# mbed_programmer.net
KiCad netlist of a schematic drawn in EAGLE
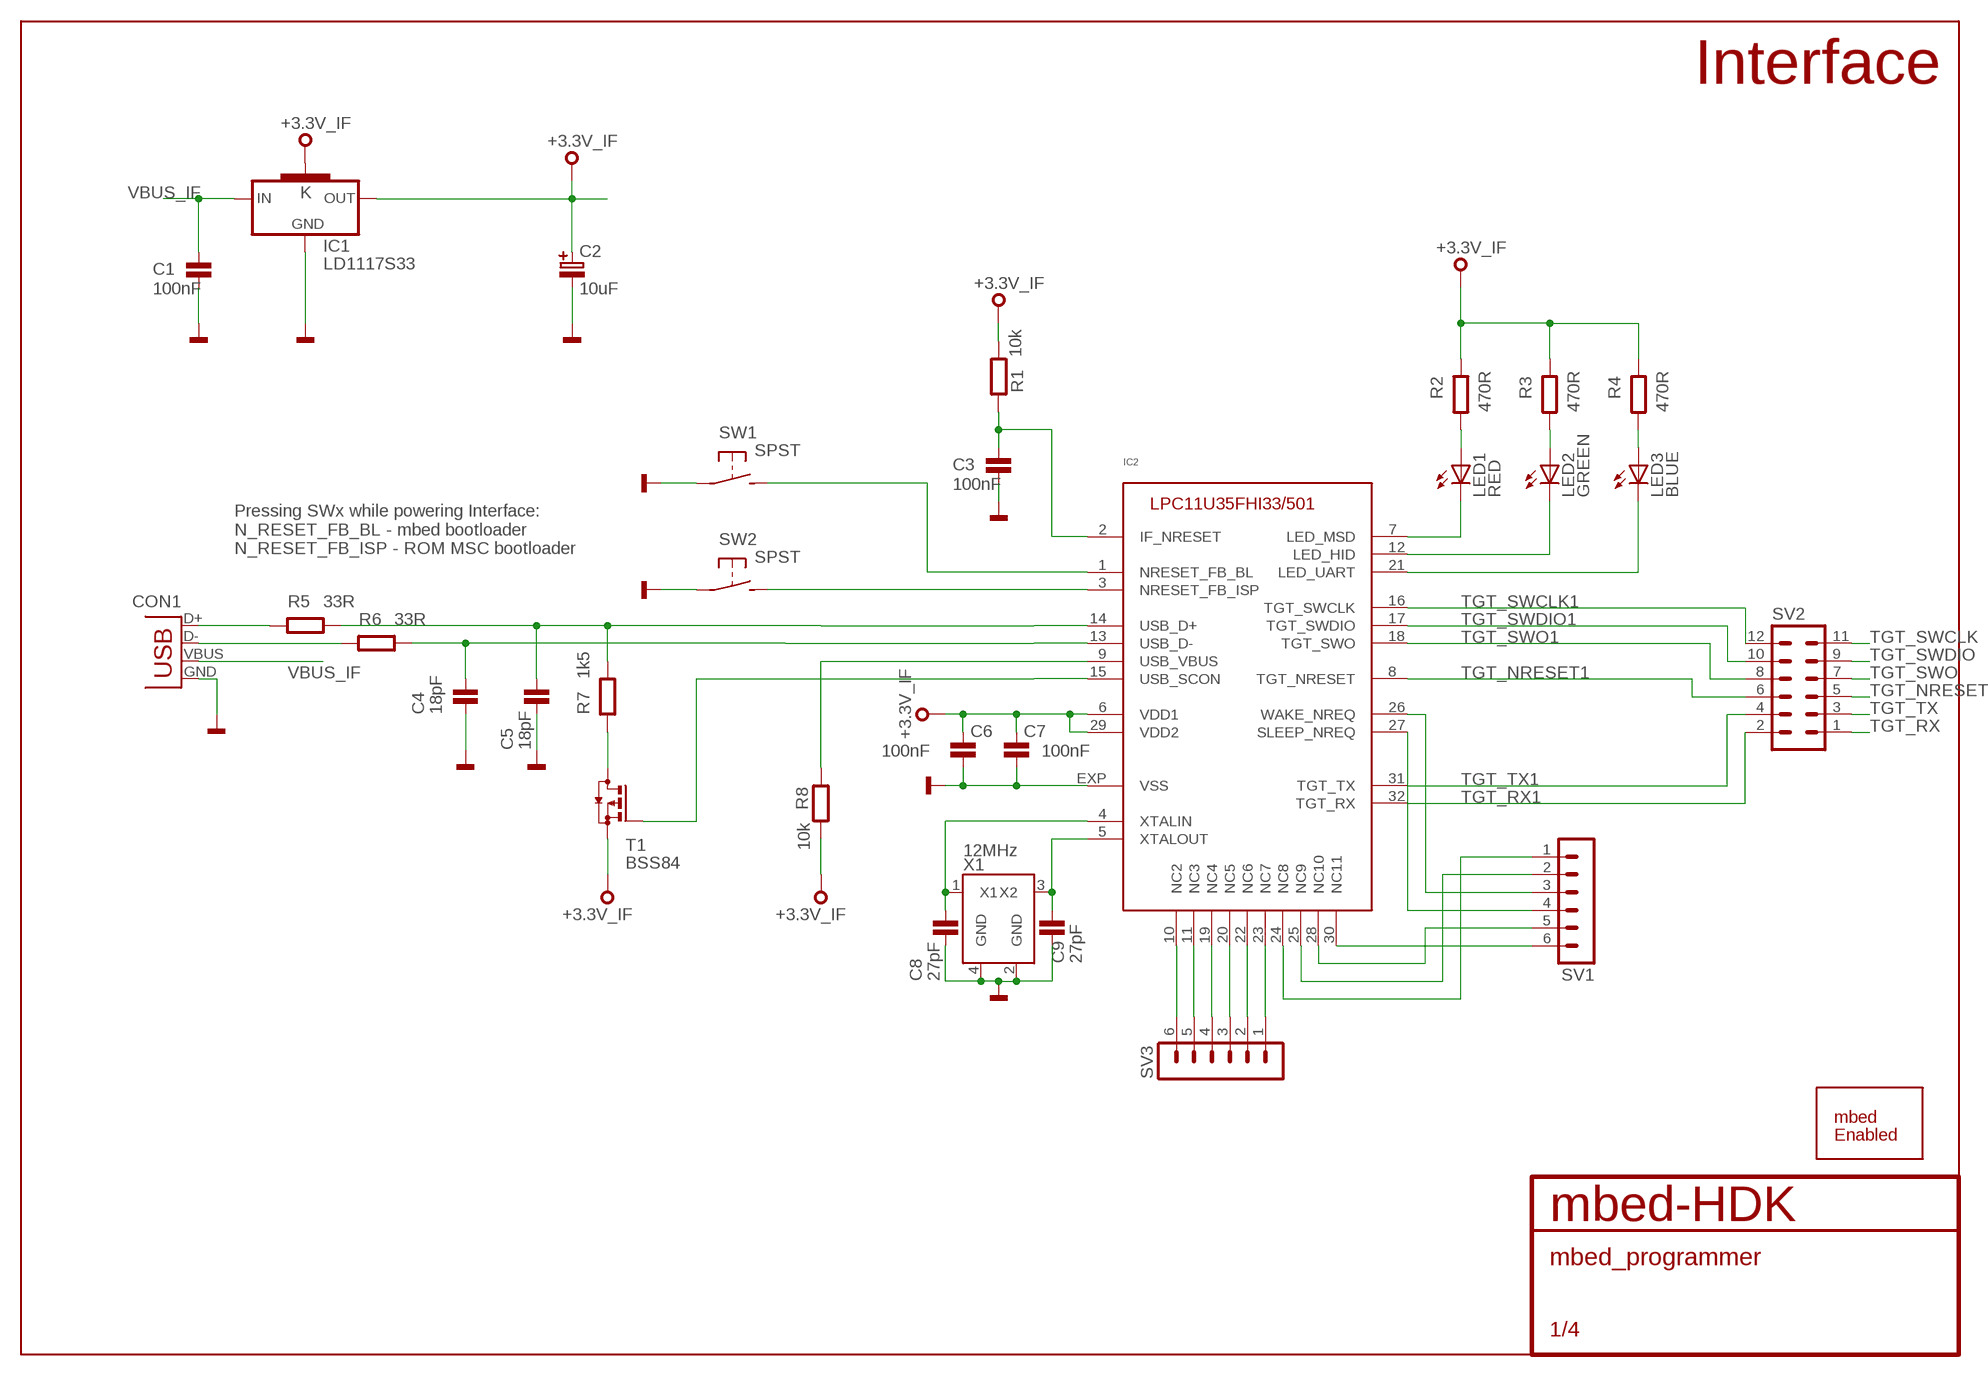
[diagram p0: schematic, sheet 1]
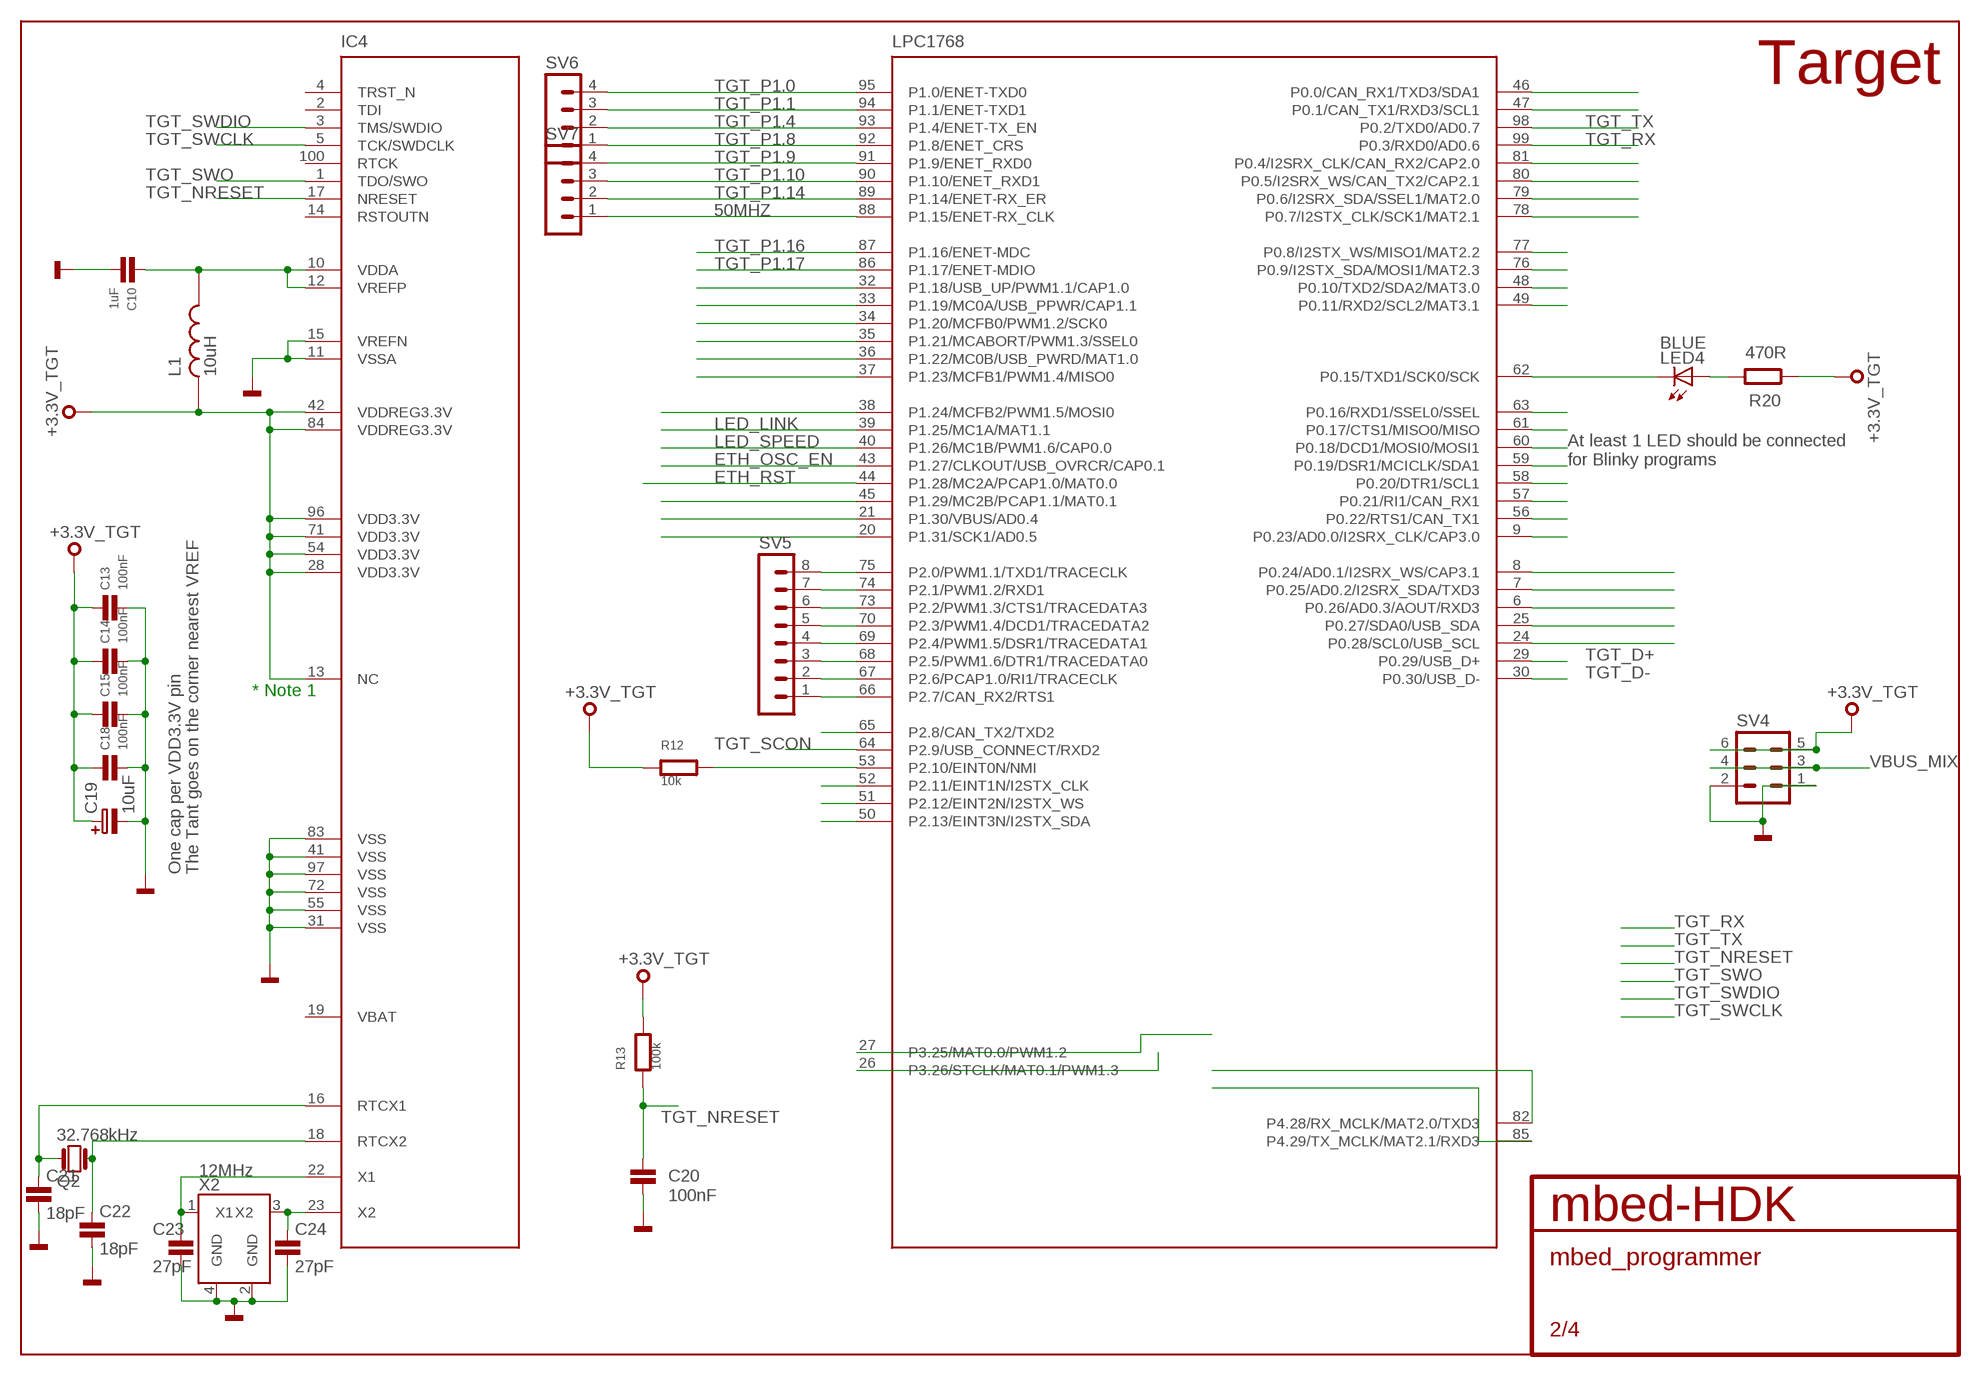
[diagram p1: schematic, sheet 2]
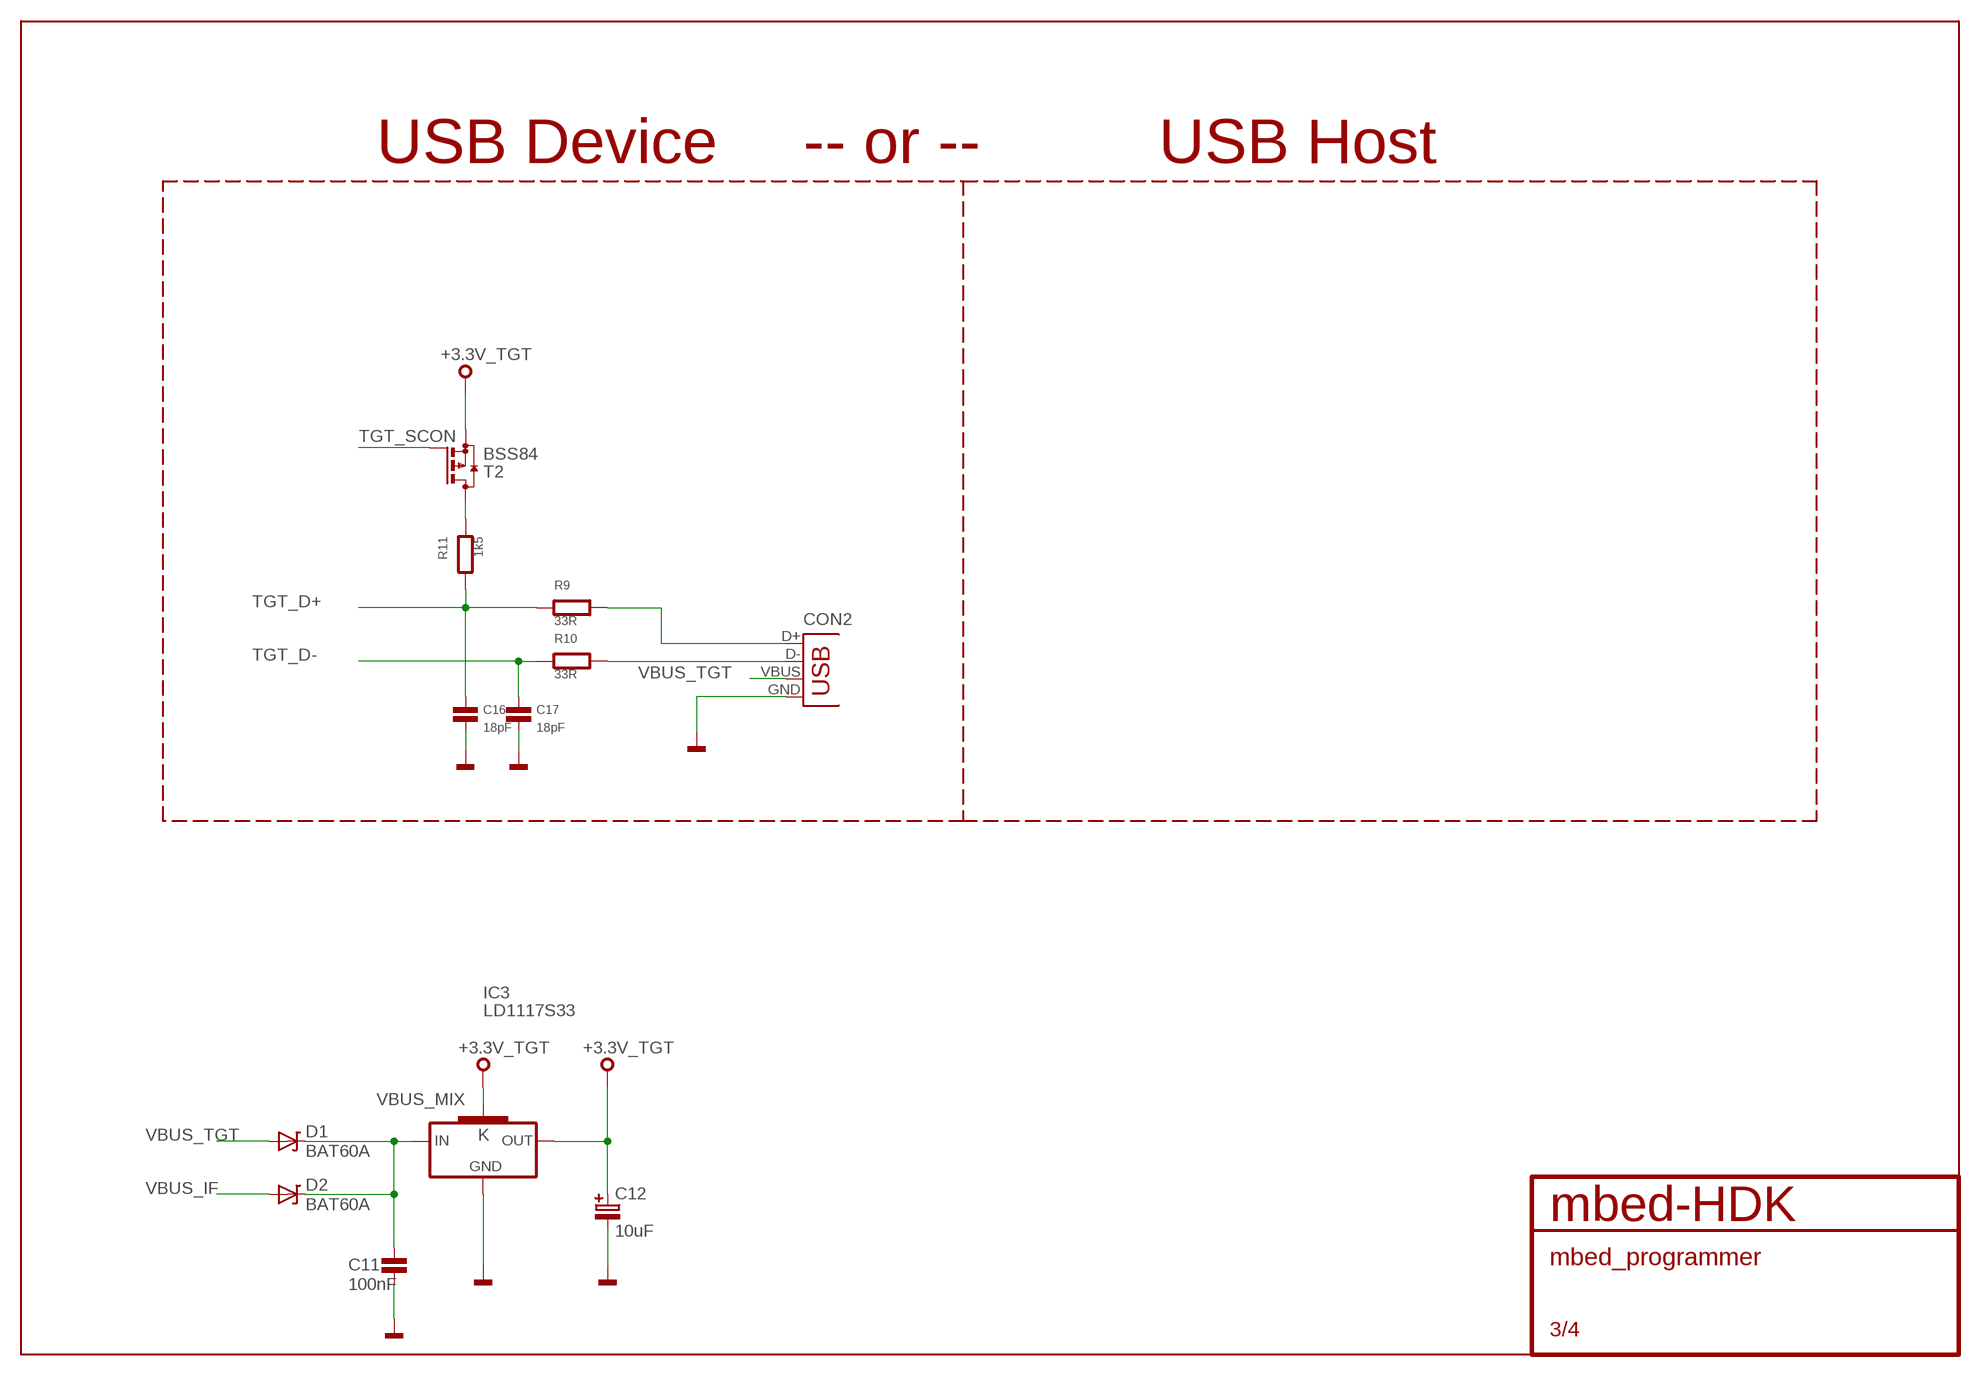
[diagram p2: schematic, sheet 3]
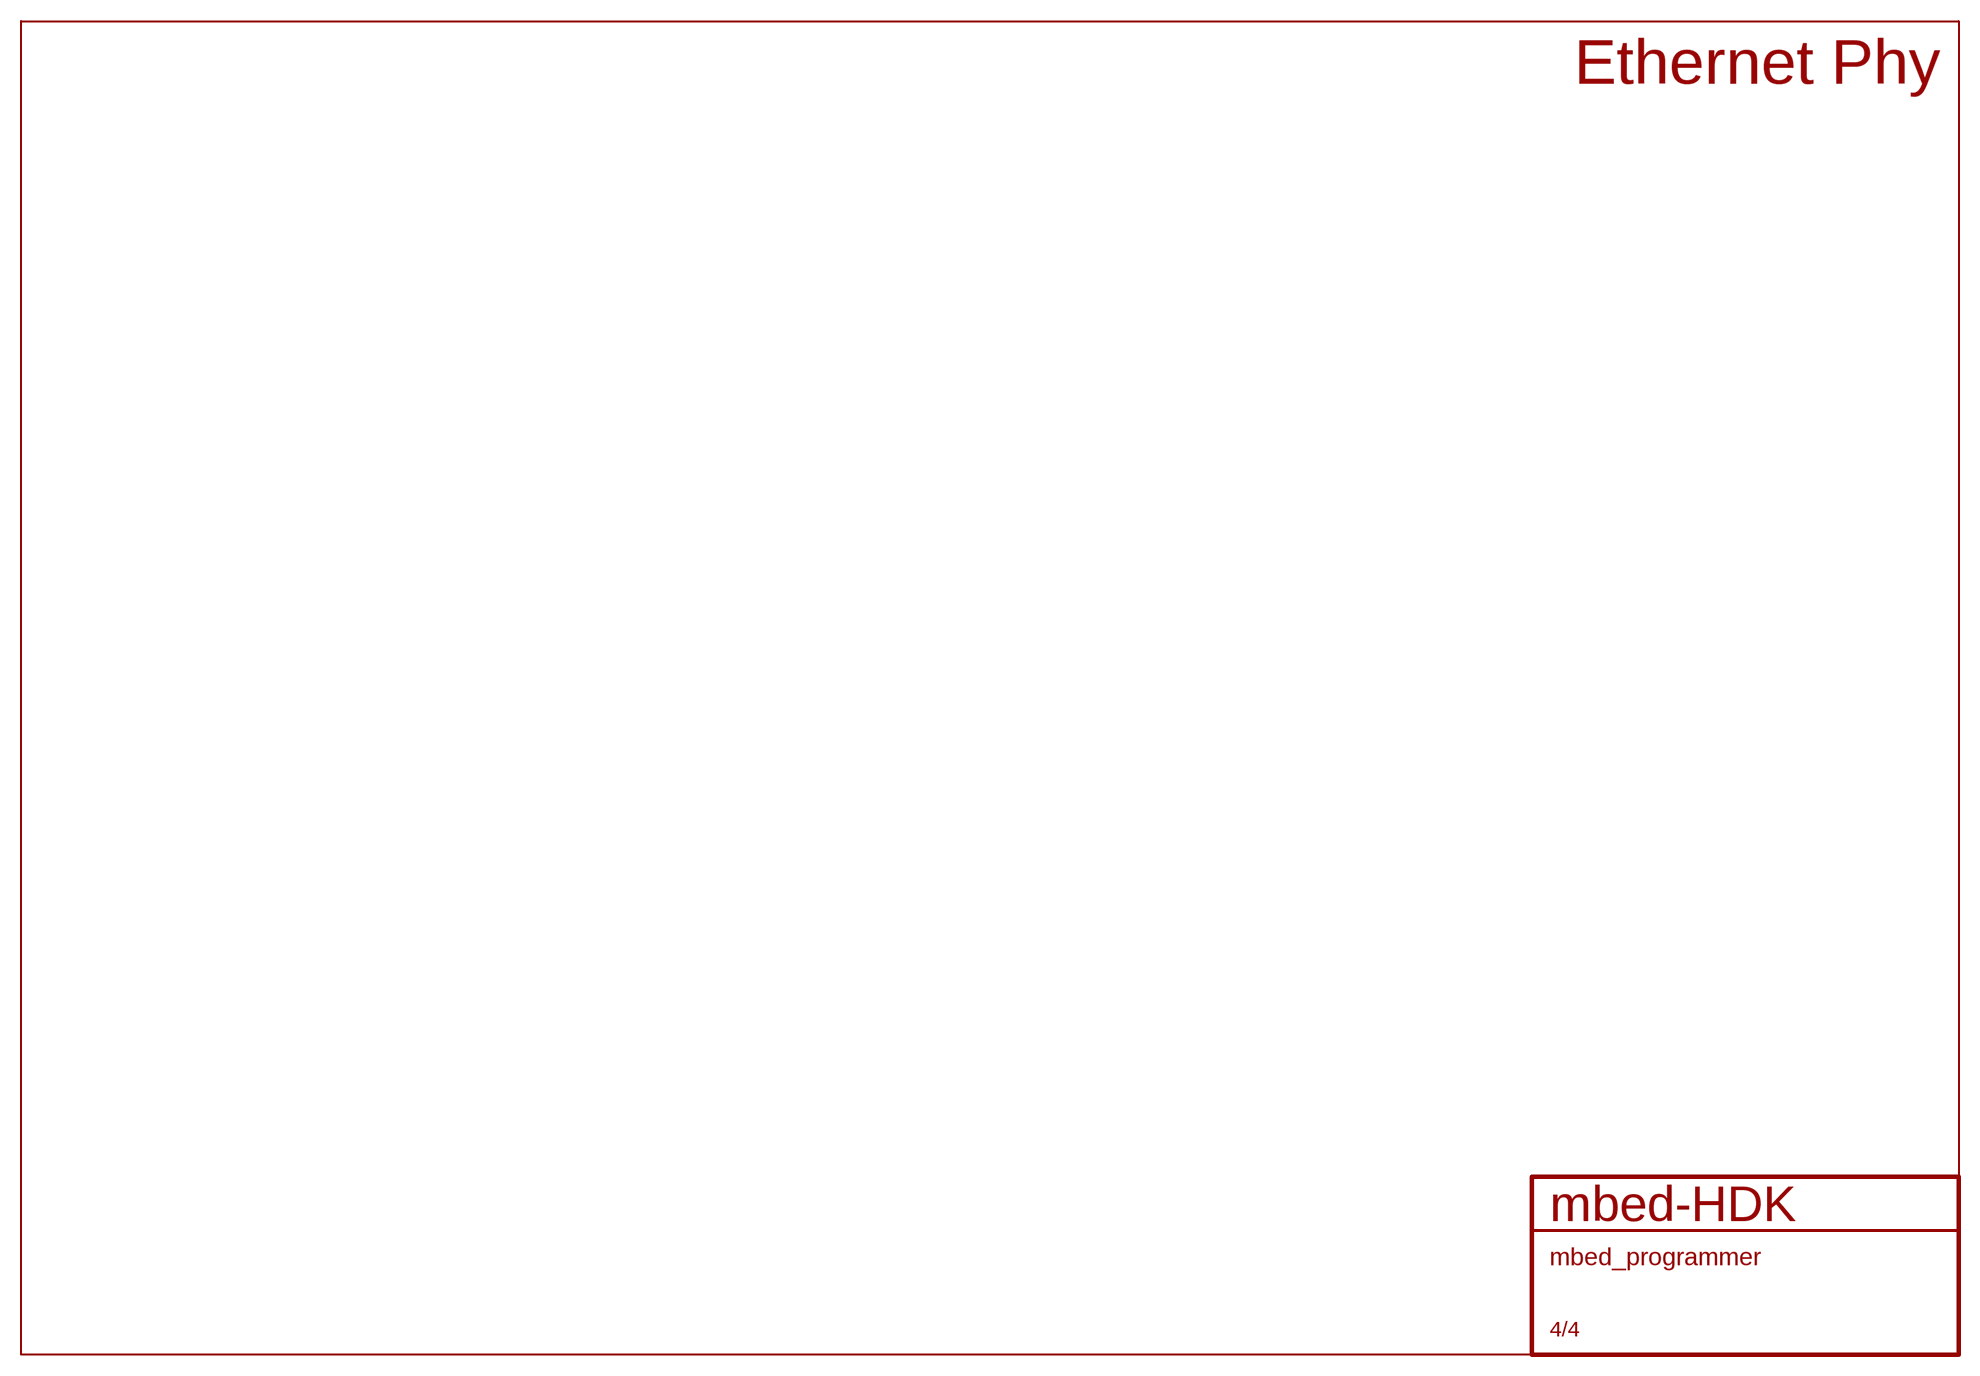
[diagram p3: schematic, sheet 4]

(export (version "E")
  (design (tool "Eeschema 10.0.6"))
  (components
    (comp (ref "C10")
      (value "1uF")
      (footprint "eagle-import:0603")
      (libsource (lib "eagle-import") (part "C0603"))
    )
    (comp (ref "C13")
      (value "100nF")
      (footprint "eagle-import:0603")
      (libsource (lib "eagle-import") (part "C0603"))
    )
    (comp (ref "C14")
      (value "100nF")
      (footprint "eagle-import:0603")
      (libsource (lib "eagle-import") (part "C0603"))
    )
    (comp (ref "C15")
      (value "100nF")
      (footprint "eagle-import:0603")
      (libsource (lib "eagle-import") (part "C0603"))
    )
    (comp (ref "C18")
      (value "100nF")
      (footprint "eagle-import:0603")
      (libsource (lib "eagle-import") (part "C0603"))
    )
    (comp (ref "C19")
      (value "10uF")
      (footprint "eagle-import:CASE-B")
      (libsource (lib "eagle-import") (part "C-POLB"))
    )
    (comp (ref "C20")
      (value "100nF")
      (footprint "eagle-import:0603")
      (libsource (lib "eagle-import") (part "C0603"))
    )
    (comp (ref "C21")
      (value "18pF")
      (footprint "eagle-import:0603")
      (libsource (lib "eagle-import") (part "C0603"))
    )
    (comp (ref "C22")
      (value "18pF")
      (footprint "eagle-import:0603")
      (libsource (lib "eagle-import") (part "C0603"))
    )
    (comp (ref "C23")
      (value "27pF")
      (footprint "eagle-import:0603")
      (libsource (lib "eagle-import") (part "C0603"))
    )
    (comp (ref "C24")
      (value "27pF")
      (footprint "eagle-import:0603")
      (libsource (lib "eagle-import") (part "C0603"))
    )
    (comp (ref "IC4")
      (value "LPC1768")
      (footprint "eagle-import:LQFP100")
      (libsource (lib "eagle-import") (part "LPC1768"))
    )
    (comp (ref "L1")
      (value "10uH")
      (footprint "eagle-import:0603")
      (libsource (lib "eagle-import") (part "L"))
    )
    (comp (ref "LED4")
      (value "BLUE")
      (footprint "eagle-import:CHIPLED_0603")
      (libsource (lib "eagle-import") (part "LED0603"))
    )
    (comp (ref "Q2")
      (value "32.768kHz")
      (footprint "eagle-import:FC135")
      (libsource (lib "eagle-import") (part "Q_FC135"))
    )
    (comp (ref "R12")
      (value "10k")
      (footprint "eagle-import:0603")
      (libsource (lib "eagle-import") (part "R0603"))
    )
    (comp (ref "R13")
      (value "100k")
      (footprint "eagle-import:0603")
      (libsource (lib "eagle-import") (part "R0603"))
    )
    (comp (ref "R20")
      (value "470R")
      (footprint "eagle-import:0603")
      (libsource (lib "eagle-import") (part "R0603"))
    )
    (comp (ref "SV4")
      (value "MA03-2")
      (footprint "eagle-import:MA03-2")
      (libsource (lib "eagle-import") (part "MA03-2"))
    )
    (comp (ref "SV5")
      (value "MA08-1")
      (footprint "eagle-import:MA08-1")
      (libsource (lib "eagle-import") (part "MA08-1"))
    )
    (comp (ref "SV6")
      (value "MA04-1")
      (footprint "eagle-import:MA04-1")
      (libsource (lib "eagle-import") (part "MA04-1"))
    )
    (comp (ref "SV7")
      (value "MA04-1")
      (footprint "eagle-import:MA04-1")
      (libsource (lib "eagle-import") (part "MA04-1"))
    )
    (comp (ref "X2")
      (value "12MHz")
      (footprint "eagle-import:OSC_CMD_32_25")
      (libsource (lib "eagle-import") (part "ABM8"))
    )
    (comp (ref "C1")
      (value "100nF")
      (footprint "eagle-import:0603")
      (libsource (lib "eagle-import") (part "C0603"))
    )
    (comp (ref "C2")
      (value "10uF")
      (footprint "eagle-import:CASE-B")
      (libsource (lib "eagle-import") (part "C-POLB"))
    )
    (comp (ref "C3")
      (value "100nF")
      (footprint "eagle-import:0603")
      (libsource (lib "eagle-import") (part "C0603"))
    )
    (comp (ref "C4")
      (value "18pF")
      (footprint "eagle-import:0603")
      (libsource (lib "eagle-import") (part "C0603"))
    )
    (comp (ref "C5")
      (value "18pF")
      (footprint "eagle-import:0603")
      (libsource (lib "eagle-import") (part "C0603"))
    )
    (comp (ref "C6")
      (value "100nF")
      (footprint "eagle-import:0603")
      (libsource (lib "eagle-import") (part "C0603"))
    )
    (comp (ref "C7")
      (value "100nF")
      (footprint "eagle-import:0603")
      (libsource (lib "eagle-import") (part "C0603"))
    )
    (comp (ref "C8")
      (value "27pF")
      (footprint "eagle-import:0603")
      (libsource (lib "eagle-import") (part "C0603"))
    )
    (comp (ref "C9")
      (value "27pF")
      (footprint "eagle-import:0603")
      (libsource (lib "eagle-import") (part "C0603"))
    )
    (comp (ref "CON1")
      (value "USB-MB-S")
      (footprint "eagle-import:USB-MB-S")
      (libsource (lib "eagle-import") (part "USB-MB-S"))
    )
    (comp (ref "IC1")
      (value "LD1117S33")
      (footprint "eagle-import:SOT223")
      (libsource (lib "eagle-import") (part "LD1117S33"))
    )
    (comp (ref "IC2")
      (value "IF-LPC11U35")
      (footprint "eagle-import:HVQFN33")
      (libsource (lib "eagle-import") (part "IF-LPC11U35"))
    )
    (comp (ref "LED1")
      (value "RED")
      (footprint "eagle-import:CHIPLED_0603")
      (libsource (lib "eagle-import") (part "LED0603"))
    )
    (comp (ref "LED2")
      (value "GREEN")
      (footprint "eagle-import:CHIPLED_0603")
      (libsource (lib "eagle-import") (part "LED0603"))
    )
    (comp (ref "LED3")
      (value "BLUE")
      (footprint "eagle-import:CHIPLED_0603")
      (libsource (lib "eagle-import") (part "LED0603"))
    )
    (comp (ref "R1")
      (value "10k")
      (footprint "eagle-import:0603")
      (libsource (lib "eagle-import") (part "R0603"))
    )
    (comp (ref "R2")
      (value "470R")
      (footprint "eagle-import:0603")
      (libsource (lib "eagle-import") (part "R0603"))
    )
    (comp (ref "R3")
      (value "470R")
      (footprint "eagle-import:0603")
      (libsource (lib "eagle-import") (part "R0603"))
    )
    (comp (ref "R4")
      (value "470R")
      (footprint "eagle-import:0603")
      (libsource (lib "eagle-import") (part "R0603"))
    )
    (comp (ref "R5")
      (value "33R")
      (footprint "eagle-import:0603")
      (libsource (lib "eagle-import") (part "R0603"))
    )
    (comp (ref "R6")
      (value "33R")
      (footprint "eagle-import:0603")
      (libsource (lib "eagle-import") (part "R0603"))
    )
    (comp (ref "R7")
      (value "1k5")
      (footprint "eagle-import:0603")
      (libsource (lib "eagle-import") (part "R0603"))
    )
    (comp (ref "R8")
      (value "10k")
      (footprint "eagle-import:0603")
      (libsource (lib "eagle-import") (part "R0603"))
    )
    (comp (ref "SS1")
      (value "MBED-ENABLED-LOGOMEDIUM")
      (footprint "eagle-import:MBED-ENABLED-LOGO-500X500-MIL")
      (libsource (lib "eagle-import") (part "MBED-ENABLED-LOGOMEDIUM"))
    )
    (comp (ref "SV1")
      (value "MA06-1")
      (footprint "eagle-import:MA06-1")
      (libsource (lib "eagle-import") (part "MA06-1"))
    )
    (comp (ref "SV2")
      (value "MA06-2")
      (footprint "eagle-import:MA06-2")
      (libsource (lib "eagle-import") (part "MA06-2"))
    )
    (comp (ref "SV3")
      (value "MA06-1")
      (footprint "eagle-import:MA06-1")
      (libsource (lib "eagle-import") (part "MA06-1"))
    )
    (comp (ref "SW1")
      (value "SPST")
      (footprint "eagle-import:DTSM-32S-B")
      (libsource (lib "eagle-import") (part "SPST"))
    )
    (comp (ref "SW2")
      (value "SPST")
      (footprint "eagle-import:DTSM-32S-B")
      (libsource (lib "eagle-import") (part "SPST"))
    )
    (comp (ref "T1")
      (value "BSS84")
      (footprint "eagle-import:SOT23")
      (libsource (lib "eagle-import") (part "BSS84"))
    )
    (comp (ref "X1")
      (value "12MHz")
      (footprint "eagle-import:OSC_CMD_32_25")
      (libsource (lib "eagle-import") (part "ABM8"))
    )
    (comp (ref "C11")
      (value "100nF")
      (footprint "eagle-import:0603")
      (libsource (lib "eagle-import") (part "C0603"))
    )
    (comp (ref "C12")
      (value "10uF")
      (footprint "eagle-import:CASE-B")
      (libsource (lib "eagle-import") (part "C-POLB"))
    )
    (comp (ref "C16")
      (value "18pF")
      (footprint "eagle-import:0603")
      (libsource (lib "eagle-import") (part "C0603"))
    )
    (comp (ref "C17")
      (value "18pF")
      (footprint "eagle-import:0603")
      (libsource (lib "eagle-import") (part "C0603"))
    )
    (comp (ref "CON2")
      (value "USB-MB-S")
      (footprint "eagle-import:USB-MB-S")
      (libsource (lib "eagle-import") (part "USB-MB-S"))
    )
    (comp (ref "D1")
      (value "BAT60A")
      (footprint "eagle-import:BAT60A")
      (libsource (lib "eagle-import") (part "BAT60A"))
    )
    (comp (ref "D2")
      (value "BAT60A")
      (footprint "eagle-import:BAT60A")
      (libsource (lib "eagle-import") (part "BAT60A"))
    )
    (comp (ref "IC3")
      (value "LD1117S33")
      (footprint "eagle-import:SOT223")
      (libsource (lib "eagle-import") (part "LD1117S33"))
    )
    (comp (ref "R9")
      (value "33R")
      (footprint "eagle-import:0603")
      (libsource (lib "eagle-import") (part "R0603"))
    )
    (comp (ref "R10")
      (value "33R")
      (footprint "eagle-import:0603")
      (libsource (lib "eagle-import") (part "R0603"))
    )
    (comp (ref "R11")
      (value "1k5")
      (footprint "eagle-import:0603")
      (libsource (lib "eagle-import") (part "R0603"))
    )
    (comp (ref "T2")
      (value "BSS84")
      (footprint "eagle-import:SOT23")
      (libsource (lib "eagle-import") (part "BSS84"))
    )
  )
  (nets
    (net (code "1") (name "+3.3V_IF") (class "Default")
      (node (ref "C2") (pin "1") (pinfunction "1_1") (pintype "passive"))
      (node (ref "C6") (pin "1") (pinfunction "P$1_1") (pintype "passive"))
      (node (ref "C7") (pin "1") (pinfunction "P$1_1") (pintype "passive"))
      (node (ref "IC1") (pin "2") (pinfunction "OUT_2") (pintype "passive"))
      (node (ref "IC1") (pin "4") (pinfunction "K_4") (pintype "passive"))
      (node (ref "IC2") (pin "29") (pinfunction "VDD2_29") (pintype "bidirectional"))
      (node (ref "IC2") (pin "6") (pinfunction "VDD1_6") (pintype "bidirectional"))
      (node (ref "R1") (pin "2") (pinfunction "P$2_2") (pintype "passive"))
      (node (ref "R2") (pin "1") (pinfunction "P$1_1") (pintype "passive"))
      (node (ref "R3") (pin "1") (pinfunction "P$1_1") (pintype "passive"))
      (node (ref "R4") (pin "1") (pinfunction "P$1_1") (pintype "passive"))
      (node (ref "R8") (pin "2") (pinfunction "P$2_2") (pintype "passive"))
      (node (ref "T1") (pin "2") (pinfunction "S_2") (pintype "passive"))
    )
    (net (code "2") (name "+3.3V_TGT") (class "Default")
      (node (ref "C12") (pin "1") (pinfunction "1_1") (pintype "passive"))
      (node (ref "C13") (pin "1") (pinfunction "P$1_1") (pintype "passive"))
      (node (ref "C14") (pin "1") (pinfunction "P$1_1") (pintype "passive"))
      (node (ref "C15") (pin "1") (pinfunction "P$1_1") (pintype "passive"))
      (node (ref "C18") (pin "1") (pinfunction "P$1_1") (pintype "passive"))
      (node (ref "C19") (pin "1") (pinfunction "1_1") (pintype "passive"))
      (node (ref "IC3") (pin "2") (pinfunction "OUT_2") (pintype "passive"))
      (node (ref "IC3") (pin "4") (pinfunction "K_4") (pintype "passive"))
      (node (ref "IC4") (pin "13") (pinfunction "NC_13") (pintype "bidirectional"))
      (node (ref "IC4") (pin "28") (pinfunction "VDD3.3V_28") (pintype "bidirectional"))
      (node (ref "IC4") (pin "42") (pinfunction "VDDREG3.3V_42") (pintype "bidirectional"))
      (node (ref "IC4") (pin "54") (pinfunction "VDD3.3V_54") (pintype "bidirectional"))
      (node (ref "IC4") (pin "71") (pinfunction "VDD3.3V_71") (pintype "bidirectional"))
      (node (ref "IC4") (pin "84") (pinfunction "VDDREG3.3V_84") (pintype "bidirectional"))
      (node (ref "IC4") (pin "96") (pinfunction "VDD3.3V_96") (pintype "bidirectional"))
      (node (ref "L1") (pin "1") (pinfunction "P$1_1") (pintype "bidirectional"))
      (node (ref "R12") (pin "1") (pinfunction "P$1_1") (pintype "passive"))
      (node (ref "R13") (pin "2") (pinfunction "P$2_2") (pintype "passive"))
      (node (ref "R20") (pin "1") (pinfunction "P$1_1") (pintype "passive"))
      (node (ref "SV4") (pin "5") (pinfunction "5_5") (pintype "passive"))
      (node (ref "SV4") (pin "6") (pinfunction "6_6") (pintype "passive"))
      (node (ref "T2") (pin "2") (pinfunction "S_2") (pintype "passive"))
    )
    (net (code "3") (name "50MHZ") (class "Default")
      (node (ref "IC4") (pin "88") (pinfunction "P1.15/ENET-RX_CLK_88") (pintype "bidirectional"))
      (node (ref "SV7") (pin "1") (pinfunction "1_1") (pintype "passive"))
    )
    (net (code "4") (name "ETH_OSC_EN") (class "Default")
      (node (ref "IC4") (pin "43") (pinfunction "P1.27/CLKOUT/USB_OVRCR/CAP0.1_43") (pintype "bidirectional"))
    )
    (net (code "5") (name "ETH_RST") (class "Default")
      (node (ref "IC4") (pin "44") (pinfunction "P1.28/MC2A/PCAP1.0/MAT0.0_44") (pintype "bidirectional"))
    )
    (net (code "6") (name "GND") (class "Default")
      (node (ref "C1") (pin "2") (pinfunction "P$2_2") (pintype "passive"))
      (node (ref "C10") (pin "2") (pinfunction "P$2_2") (pintype "passive"))
      (node (ref "C11") (pin "2") (pinfunction "P$2_2") (pintype "passive"))
      (node (ref "C12") (pin "2") (pinfunction "2_2") (pintype "passive"))
      (node (ref "C13") (pin "2") (pinfunction "P$2_2") (pintype "passive"))
      (node (ref "C14") (pin "2") (pinfunction "P$2_2") (pintype "passive"))
      (node (ref "C15") (pin "2") (pinfunction "P$2_2") (pintype "passive"))
      (node (ref "C16") (pin "2") (pinfunction "P$2_2") (pintype "passive"))
      (node (ref "C17") (pin "2") (pinfunction "P$2_2") (pintype "passive"))
      (node (ref "C18") (pin "2") (pinfunction "P$2_2") (pintype "passive"))
      (node (ref "C19") (pin "2") (pinfunction "2_2") (pintype "passive"))
      (node (ref "C2") (pin "2") (pinfunction "2_2") (pintype "passive"))
      (node (ref "C20") (pin "1") (pinfunction "P$1_1") (pintype "passive"))
      (node (ref "C21") (pin "1") (pinfunction "P$1_1") (pintype "passive"))
      (node (ref "C22") (pin "1") (pinfunction "P$1_1") (pintype "passive"))
      (node (ref "C23") (pin "1") (pinfunction "P$1_1") (pintype "passive"))
      (node (ref "C24") (pin "1") (pinfunction "P$1_1") (pintype "passive"))
      (node (ref "C3") (pin "2") (pinfunction "P$2_2") (pintype "passive"))
      (node (ref "C4") (pin "2") (pinfunction "P$2_2") (pintype "passive"))
      (node (ref "C5") (pin "2") (pinfunction "P$2_2") (pintype "passive"))
      (node (ref "C6") (pin "2") (pinfunction "P$2_2") (pintype "passive"))
      (node (ref "C7") (pin "2") (pinfunction "P$2_2") (pintype "passive"))
      (node (ref "C8") (pin "2") (pinfunction "P$2_2") (pintype "passive"))
      (node (ref "C9") (pin "2") (pinfunction "P$2_2") (pintype "passive"))
      (node (ref "CON1") (pin "GND") (pinfunction "GND_GND") (pintype "bidirectional"))
      (node (ref "CON2") (pin "GND") (pinfunction "GND_GND") (pintype "bidirectional"))
      (node (ref "IC1") (pin "1") (pinfunction "GND_1") (pintype "input"))
      (node (ref "IC2") (pin "EXP") (pinfunction "VSS_EXP") (pintype "bidirectional"))
      (node (ref "IC3") (pin "1") (pinfunction "GND_1") (pintype "input"))
      (node (ref "IC4") (pin "11") (pinfunction "VSSA_11") (pintype "bidirectional"))
      (node (ref "IC4") (pin "15") (pinfunction "VREFN_15") (pintype "bidirectional"))
      (node (ref "IC4") (pin "31") (pinfunction "VSS_31") (pintype "bidirectional"))
      (node (ref "IC4") (pin "41") (pinfunction "VSS_41") (pintype "bidirectional"))
      (node (ref "IC4") (pin "55") (pinfunction "VSS_55") (pintype "bidirectional"))
      (node (ref "IC4") (pin "72") (pinfunction "VSS_72") (pintype "bidirectional"))
      (node (ref "IC4") (pin "83") (pinfunction "VSS_83") (pintype "bidirectional"))
      (node (ref "IC4") (pin "97") (pinfunction "VSS_97") (pintype "bidirectional"))
      (node (ref "SV4") (pin "1") (pinfunction "1_1") (pintype "passive"))
      (node (ref "SV4") (pin "2") (pinfunction "2_2") (pintype "passive"))
      (node (ref "SW1") (pin "P$1") (pinfunction "P_P$1") (pintype "passive"))
      (node (ref "SW2") (pin "P$1") (pinfunction "P_P$1") (pintype "passive"))
      (node (ref "X1") (pin "2") (pinfunction "GND_2") (pintype "bidirectional"))
      (node (ref "X1") (pin "4") (pinfunction "GND_4") (pintype "bidirectional"))
      (node (ref "X2") (pin "2") (pinfunction "GND_2") (pintype "bidirectional"))
      (node (ref "X2") (pin "4") (pinfunction "GND_4") (pintype "bidirectional"))
    )
    (net (code "7") (name "LED_LINK") (class "Default")
      (node (ref "IC4") (pin "39") (pinfunction "P1.25/MC1A/MAT1.1_39") (pintype "bidirectional"))
    )
    (net (code "8") (name "LED_SPEED") (class "Default")
      (node (ref "IC4") (pin "40") (pinfunction "P1.26/MC1B/PWM1.6/CAP0.0_40") (pintype "bidirectional"))
    )
    (net (code "9") (name "Net-(C3-P$1)") (class "Default")
      (node (ref "C3") (pin "1") (pinfunction "P$1_1") (pintype "passive"))
      (node (ref "IC2") (pin "2") (pinfunction "IF_NRESET_2") (pintype "bidirectional"))
      (node (ref "R1") (pin "1") (pinfunction "P$1_1") (pintype "passive"))
    )
    (net (code "10") (name "Net-(C4-P$1)") (class "Default")
      (node (ref "C4") (pin "1") (pinfunction "P$1_1") (pintype "passive"))
      (node (ref "IC2") (pin "13") (pinfunction "USB_D-_13") (pintype "bidirectional"))
      (node (ref "R6") (pin "2") (pinfunction "P$2_2") (pintype "passive"))
    )
    (net (code "11") (name "Net-(C5-P$1)") (class "Default")
      (node (ref "C5") (pin "1") (pinfunction "P$1_1") (pintype "passive"))
      (node (ref "IC2") (pin "14") (pinfunction "USB_D+_14") (pintype "bidirectional"))
      (node (ref "R5") (pin "2") (pinfunction "P$2_2") (pintype "passive"))
      (node (ref "R7") (pin "2") (pinfunction "P$2_2") (pintype "passive"))
    )
    (net (code "12") (name "Net-(C8-P$1)") (class "Default")
      (node (ref "C8") (pin "1") (pinfunction "P$1_1") (pintype "passive"))
      (node (ref "IC2") (pin "4") (pinfunction "XTALIN_4") (pintype "bidirectional"))
      (node (ref "X1") (pin "1") (pinfunction "X1_1") (pintype "bidirectional"))
    )
    (net (code "13") (name "Net-(C9-P$1)") (class "Default")
      (node (ref "C9") (pin "1") (pinfunction "P$1_1") (pintype "passive"))
      (node (ref "IC2") (pin "5") (pinfunction "XTALOUT_5") (pintype "bidirectional"))
      (node (ref "X1") (pin "3") (pinfunction "X2_3") (pintype "bidirectional"))
    )
    (net (code "14") (name "Net-(C10-P$1)") (class "Default")
      (node (ref "C10") (pin "1") (pinfunction "P$1_1") (pintype "passive"))
      (node (ref "IC4") (pin "10") (pinfunction "VDDA_10") (pintype "bidirectional"))
      (node (ref "IC4") (pin "12") (pinfunction "VREFP_12") (pintype "bidirectional"))
      (node (ref "L1") (pin "2") (pinfunction "P$2_2") (pintype "bidirectional"))
    )
    (net (code "15") (name "Net-(C21-P$2)") (class "Default")
      (node (ref "C21") (pin "2") (pinfunction "P$2_2") (pintype "passive"))
      (node (ref "IC4") (pin "16") (pinfunction "RTCX1_16") (pintype "bidirectional"))
      (node (ref "Q2") (pin "X2") (pinfunction "2_X2") (pintype "passive"))
    )
    (net (code "16") (name "Net-(C22-P$2)") (class "Default")
      (node (ref "C22") (pin "2") (pinfunction "P$2_2") (pintype "passive"))
      (node (ref "IC4") (pin "18") (pinfunction "RTCX2_18") (pintype "bidirectional"))
      (node (ref "Q2") (pin "X1") (pinfunction "1_X1") (pintype "passive"))
    )
    (net (code "17") (name "Net-(C23-P$2)") (class "Default")
      (node (ref "C23") (pin "2") (pinfunction "P$2_2") (pintype "passive"))
      (node (ref "IC4") (pin "22") (pinfunction "X1_22") (pintype "bidirectional"))
      (node (ref "X2") (pin "1") (pinfunction "X1_1") (pintype "bidirectional"))
    )
    (net (code "18") (name "Net-(C24-P$2)") (class "Default")
      (node (ref "C24") (pin "2") (pinfunction "P$2_2") (pintype "passive"))
      (node (ref "IC4") (pin "23") (pinfunction "X2_23") (pintype "bidirectional"))
      (node (ref "X2") (pin "3") (pinfunction "X2_3") (pintype "bidirectional"))
    )
    (net (code "19") (name "Net-(IC2-LED_HID)") (class "Default")
      (node (ref "IC2") (pin "12") (pinfunction "LED_HID_12") (pintype "bidirectional"))
      (node (ref "LED2") (pin "C") (pinfunction "C_C") (pintype "passive"))
    )
    (net (code "20") (name "Net-(IC2-LED_MSD)") (class "Default")
      (node (ref "IC2") (pin "7") (pinfunction "LED_MSD_7") (pintype "bidirectional"))
      (node (ref "LED1") (pin "C") (pinfunction "C_C") (pintype "passive"))
    )
    (net (code "21") (name "Net-(IC2-LED_UART)") (class "Default")
      (node (ref "IC2") (pin "21") (pinfunction "LED_UART_21") (pintype "bidirectional"))
      (node (ref "LED3") (pin "C") (pinfunction "C_C") (pintype "passive"))
    )
    (net (code "22") (name "Net-(IC2-NC2)") (class "Default")
      (node (ref "IC2") (pin "10") (pinfunction "NC2_10") (pintype "bidirectional"))
      (node (ref "SV3") (pin "6") (pinfunction "6_6") (pintype "passive"))
    )
    (net (code "23") (name "Net-(IC2-NC3)") (class "Default")
      (node (ref "IC2") (pin "11") (pinfunction "NC3_11") (pintype "bidirectional"))
      (node (ref "SV3") (pin "5") (pinfunction "5_5") (pintype "passive"))
    )
    (net (code "24") (name "Net-(IC2-NC4)") (class "Default")
      (node (ref "IC2") (pin "19") (pinfunction "NC4_19") (pintype "bidirectional"))
      (node (ref "SV3") (pin "4") (pinfunction "4_4") (pintype "passive"))
    )
    (net (code "25") (name "Net-(IC2-NC5)") (class "Default")
      (node (ref "IC2") (pin "20") (pinfunction "NC5_20") (pintype "bidirectional"))
      (node (ref "SV3") (pin "3") (pinfunction "3_3") (pintype "passive"))
    )
    (net (code "26") (name "Net-(IC2-NC6)") (class "Default")
      (node (ref "IC2") (pin "22") (pinfunction "NC6_22") (pintype "bidirectional"))
      (node (ref "SV3") (pin "2") (pinfunction "2_2") (pintype "passive"))
    )
    (net (code "27") (name "Net-(IC2-NC7)") (class "Default")
      (node (ref "IC2") (pin "23") (pinfunction "NC7_23") (pintype "bidirectional"))
      (node (ref "SV3") (pin "1") (pinfunction "1_1") (pintype "passive"))
    )
    (net (code "28") (name "Net-(IC2-NC8)") (class "Default")
      (node (ref "IC2") (pin "24") (pinfunction "NC8_24") (pintype "bidirectional"))
      (node (ref "SV1") (pin "1") (pinfunction "1_1") (pintype "passive"))
    )
    (net (code "29") (name "Net-(IC2-NC9)") (class "Default")
      (node (ref "IC2") (pin "25") (pinfunction "NC9_25") (pintype "bidirectional"))
      (node (ref "SV1") (pin "2") (pinfunction "2_2") (pintype "passive"))
    )
    (net (code "30") (name "Net-(IC2-NC10)") (class "Default")
      (node (ref "IC2") (pin "28") (pinfunction "NC10_28") (pintype "bidirectional"))
      (node (ref "SV1") (pin "5") (pinfunction "5_5") (pintype "passive"))
    )
    (net (code "31") (name "Net-(IC2-NC11)") (class "Default")
      (node (ref "IC2") (pin "30") (pinfunction "NC11_30") (pintype "bidirectional"))
      (node (ref "SV1") (pin "6") (pinfunction "6_6") (pintype "passive"))
    )
    (net (code "32") (name "Net-(IC2-NRESET_FB_BL)") (class "Default")
      (node (ref "IC2") (pin "1") (pinfunction "NRESET_FB_BL_1") (pintype "bidirectional"))
      (node (ref "SW1") (pin "P$2") (pinfunction "S_P$2") (pintype "passive"))
    )
    (net (code "33") (name "Net-(IC2-NRESET_FB_ISP)") (class "Default")
      (node (ref "IC2") (pin "3") (pinfunction "NRESET_FB_ISP_3") (pintype "bidirectional"))
      (node (ref "SW2") (pin "P$2") (pinfunction "S_P$2") (pintype "passive"))
    )
    (net (code "34") (name "Net-(IC2-SLEEP_NREQ)") (class "Default")
      (node (ref "IC2") (pin "27") (pinfunction "SLEEP_NREQ_27") (pintype "bidirectional"))
      (node (ref "SV1") (pin "4") (pinfunction "4_4") (pintype "passive"))
    )
    (net (code "35") (name "Net-(IC2-USB_SCON)") (class "Default")
      (node (ref "IC2") (pin "15") (pinfunction "USB_SCON_15") (pintype "bidirectional"))
      (node (ref "T1") (pin "1") (pinfunction "G_1") (pintype "passive"))
    )
    (net (code "36") (name "Net-(IC2-USB_VBUS)") (class "Default")
      (node (ref "IC2") (pin "9") (pinfunction "USB_VBUS_9") (pintype "bidirectional"))
      (node (ref "R8") (pin "1") (pinfunction "P$1_1") (pintype "passive"))
    )
    (net (code "37") (name "Net-(IC2-WAKE_NREQ)") (class "Default")
      (node (ref "IC2") (pin "26") (pinfunction "WAKE_NREQ_26") (pintype "bidirectional"))
      (node (ref "SV1") (pin "3") (pinfunction "3_3") (pintype "passive"))
    )
    (net (code "38") (name "Net-(IC4-P0.15{slash}TXD1{slash}SCK0{slash}SCK)") (class "Default")
      (node (ref "IC4") (pin "62") (pinfunction "P0.15/TXD1/SCK0/SCK_62") (pintype "bidirectional"))
      (node (ref "LED4") (pin "C") (pinfunction "C_C") (pintype "passive"))
    )
    (net (code "39") (name "Net-(IC4-P2.0{slash}PWM1.1{slash}TXD1{slash}TRACECLK)") (class "Default")
      (node (ref "IC4") (pin "75") (pinfunction "P2.0/PWM1.1/TXD1/TRACECLK_75") (pintype "bidirectional"))
      (node (ref "SV5") (pin "8") (pinfunction "8_8") (pintype "passive"))
    )
    (net (code "40") (name "Net-(IC4-P2.1{slash}PWM1.2{slash}RXD1)") (class "Default")
      (node (ref "IC4") (pin "74") (pinfunction "P2.1/PWM1.2/RXD1_74") (pintype "bidirectional"))
      (node (ref "SV5") (pin "7") (pinfunction "7_7") (pintype "passive"))
    )
    (net (code "41") (name "Net-(IC4-P2.2{slash}PWM1.3{slash}CTS1{slash}TRACEDATA3)") (class "Default")
      (node (ref "IC4") (pin "73") (pinfunction "P2.2/PWM1.3/CTS1/TRACEDATA3_73") (pintype "bidirectional"))
      (node (ref "SV5") (pin "6") (pinfunction "6_6") (pintype "passive"))
    )
    (net (code "42") (name "Net-(IC4-P2.3{slash}PWM1.4{slash}DCD1{slash}TRACEDATA2)") (class "Default")
      (node (ref "IC4") (pin "70") (pinfunction "P2.3/PWM1.4/DCD1/TRACEDATA2_70") (pintype "bidirectional"))
      (node (ref "SV5") (pin "5") (pinfunction "5_5") (pintype "passive"))
    )
    (net (code "43") (name "Net-(IC4-P2.4{slash}PWM1.5{slash}DSR1{slash}TRACEDATA1)") (class "Default")
      (node (ref "IC4") (pin "69") (pinfunction "P2.4/PWM1.5/DSR1/TRACEDATA1_69") (pintype "bidirectional"))
      (node (ref "SV5") (pin "4") (pinfunction "4_4") (pintype "passive"))
    )
    (net (code "44") (name "Net-(IC4-P2.5{slash}PWM1.6{slash}DTR1{slash}TRACEDATA0)") (class "Default")
      (node (ref "IC4") (pin "68") (pinfunction "P2.5/PWM1.6/DTR1/TRACEDATA0_68") (pintype "bidirectional"))
      (node (ref "SV5") (pin "3") (pinfunction "3_3") (pintype "passive"))
    )
    (net (code "45") (name "Net-(IC4-P2.6{slash}PCAP1.0{slash}RI1{slash}TRACECLK)") (class "Default")
      (node (ref "IC4") (pin "67") (pinfunction "P2.6/PCAP1.0/RI1/TRACECLK_67") (pintype "bidirectional"))
      (node (ref "SV5") (pin "2") (pinfunction "2_2") (pintype "passive"))
    )
    (net (code "46") (name "Net-(IC4-P2.7{slash}CAN_RX2{slash}RTS1)") (class "Default")
      (node (ref "IC4") (pin "66") (pinfunction "P2.7/CAN_RX2/RTS1_66") (pintype "bidirectional"))
      (node (ref "SV5") (pin "1") (pinfunction "1_1") (pintype "passive"))
    )
    (net (code "47") (name "Net-(IC4-P2.10{slash}EINT0N{slash}NMI)") (class "Default")
      (node (ref "IC4") (pin "53") (pinfunction "P2.10/EINT0N/NMI_53") (pintype "bidirectional"))
      (node (ref "R12") (pin "2") (pinfunction "P$2_2") (pintype "passive"))
    )
    (net (code "48") (name "Net-(R2-P$2)") (class "Default")
      (node (ref "LED1") (pin "A") (pinfunction "A_A") (pintype "passive"))
      (node (ref "R2") (pin "2") (pinfunction "P$2_2") (pintype "passive"))
    )
    (net (code "49") (name "Net-(R3-P$2)") (class "Default")
      (node (ref "LED2") (pin "A") (pinfunction "A_A") (pintype "passive"))
      (node (ref "R3") (pin "2") (pinfunction "P$2_2") (pintype "passive"))
    )
    (net (code "50") (name "Net-(R4-P$2)") (class "Default")
      (node (ref "LED3") (pin "A") (pinfunction "A_A") (pintype "passive"))
      (node (ref "R4") (pin "2") (pinfunction "P$2_2") (pintype "passive"))
    )
    (net (code "51") (name "Net-(R5-P$1)") (class "Default")
      (node (ref "CON1") (pin "D+") (pinfunction "D+_D+") (pintype "bidirectional"))
      (node (ref "R5") (pin "1") (pinfunction "P$1_1") (pintype "passive"))
    )
    (net (code "52") (name "Net-(R6-P$1)") (class "Default")
      (node (ref "CON1") (pin "D-") (pinfunction "D-_D-") (pintype "bidirectional"))
      (node (ref "R6") (pin "1") (pinfunction "P$1_1") (pintype "passive"))
    )
    (net (code "53") (name "Net-(R7-P$1)") (class "Default")
      (node (ref "R7") (pin "1") (pinfunction "P$1_1") (pintype "passive"))
      (node (ref "T1") (pin "3") (pinfunction "D_3") (pintype "passive"))
    )
    (net (code "54") (name "Net-(R9-P$2)") (class "Default")
      (node (ref "CON2") (pin "D+") (pinfunction "D+_D+") (pintype "bidirectional"))
      (node (ref "R9") (pin "2") (pinfunction "P$2_2") (pintype "passive"))
    )
    (net (code "55") (name "Net-(R10-P$2)") (class "Default")
      (node (ref "CON2") (pin "D-") (pinfunction "D-_D-") (pintype "bidirectional"))
      (node (ref "R10") (pin "2") (pinfunction "P$2_2") (pintype "passive"))
    )
    (net (code "56") (name "Net-(R11-P$1)") (class "Default")
      (node (ref "R11") (pin "1") (pinfunction "P$1_1") (pintype "passive"))
      (node (ref "T2") (pin "3") (pinfunction "D_3") (pintype "passive"))
    )
    (net (code "57") (name "Net-(R20-P$2)") (class "Default")
      (node (ref "LED4") (pin "A") (pinfunction "A_A") (pintype "passive"))
      (node (ref "R20") (pin "2") (pinfunction "P$2_2") (pintype "passive"))
    )
    (net (code "58") (name "TGT_D+") (class "Default")
      (node (ref "C16") (pin "1") (pinfunction "P$1_1") (pintype "passive"))
      (node (ref "IC4") (pin "29") (pinfunction "P0.29/USB_D+_29") (pintype "bidirectional"))
      (node (ref "R11") (pin "2") (pinfunction "P$2_2") (pintype "passive"))
      (node (ref "R9") (pin "1") (pinfunction "P$1_1") (pintype "passive"))
    )
    (net (code "59") (name "TGT_D-") (class "Default")
      (node (ref "C17") (pin "1") (pinfunction "P$1_1") (pintype "passive"))
      (node (ref "IC4") (pin "30") (pinfunction "P0.30/USB_D-_30") (pintype "bidirectional"))
      (node (ref "R10") (pin "1") (pinfunction "P$1_1") (pintype "passive"))
    )
    (net (code "60") (name "TGT_NRESET") (class "Default")
      (node (ref "C20") (pin "2") (pinfunction "P$2_2") (pintype "passive"))
      (node (ref "IC4") (pin "17") (pinfunction "NRESET_17") (pintype "bidirectional"))
      (node (ref "R13") (pin "1") (pinfunction "P$1_1") (pintype "passive"))
      (node (ref "SV2") (pin "5") (pinfunction "5_5") (pintype "passive"))
    )
    (net (code "61") (name "TGT_NRESET1") (class "Default")
      (node (ref "IC2") (pin "8") (pinfunction "TGT_NRESET_8") (pintype "bidirectional"))
      (node (ref "SV2") (pin "6") (pinfunction "6_6") (pintype "passive"))
    )
    (net (code "62") (name "TGT_P1.0") (class "Default")
      (node (ref "IC4") (pin "95") (pinfunction "P1.0/ENET-TXD0_95") (pintype "bidirectional"))
      (node (ref "SV6") (pin "4") (pinfunction "4_4") (pintype "passive"))
    )
    (net (code "63") (name "TGT_P1.1") (class "Default")
      (node (ref "IC4") (pin "94") (pinfunction "P1.1/ENET-TXD1_94") (pintype "bidirectional"))
      (node (ref "SV6") (pin "3") (pinfunction "3_3") (pintype "passive"))
    )
    (net (code "64") (name "TGT_P1.4") (class "Default")
      (node (ref "IC4") (pin "93") (pinfunction "P1.4/ENET-TX_EN_93") (pintype "bidirectional"))
      (node (ref "SV6") (pin "2") (pinfunction "2_2") (pintype "passive"))
    )
    (net (code "65") (name "TGT_P1.8") (class "Default")
      (node (ref "IC4") (pin "92") (pinfunction "P1.8/ENET_CRS_92") (pintype "bidirectional"))
      (node (ref "SV6") (pin "1") (pinfunction "1_1") (pintype "passive"))
    )
    (net (code "66") (name "TGT_P1.9") (class "Default")
      (node (ref "IC4") (pin "91") (pinfunction "P1.9/ENET_RXD0_91") (pintype "bidirectional"))
      (node (ref "SV7") (pin "4") (pinfunction "4_4") (pintype "passive"))
    )
    (net (code "67") (name "TGT_P1.10") (class "Default")
      (node (ref "IC4") (pin "90") (pinfunction "P1.10/ENET_RXD1_90") (pintype "bidirectional"))
      (node (ref "SV7") (pin "3") (pinfunction "3_3") (pintype "passive"))
    )
    (net (code "68") (name "TGT_P1.14") (class "Default")
      (node (ref "IC4") (pin "89") (pinfunction "P1.14/ENET-RX_ER_89") (pintype "bidirectional"))
      (node (ref "SV7") (pin "2") (pinfunction "2_2") (pintype "passive"))
    )
    (net (code "69") (name "TGT_P1.16") (class "Default")
      (node (ref "IC4") (pin "87") (pinfunction "P1.16/ENET-MDC_87") (pintype "bidirectional"))
    )
    (net (code "70") (name "TGT_P1.17") (class "Default")
      (node (ref "IC4") (pin "86") (pinfunction "P1.17/ENET-MDIO_86") (pintype "bidirectional"))
    )
    (net (code "71") (name "TGT_RX") (class "Default")
      (node (ref "IC4") (pin "99") (pinfunction "P0.3/RXD0/AD0.6_99") (pintype "bidirectional"))
      (node (ref "SV2") (pin "1") (pinfunction "1_1") (pintype "passive"))
    )
    (net (code "72") (name "TGT_RX1") (class "Default")
      (node (ref "IC2") (pin "32") (pinfunction "TGT_RX_32") (pintype "bidirectional"))
      (node (ref "SV2") (pin "2") (pinfunction "2_2") (pintype "passive"))
    )
    (net (code "73") (name "TGT_SCON") (class "Default")
      (node (ref "IC4") (pin "64") (pinfunction "P2.9/USB_CONNECT/RXD2_64") (pintype "bidirectional"))
      (node (ref "T2") (pin "1") (pinfunction "G_1") (pintype "passive"))
    )
    (net (code "74") (name "TGT_SWCLK") (class "Default")
      (node (ref "IC4") (pin "5") (pinfunction "TCK/SWDCLK_5") (pintype "bidirectional"))
      (node (ref "SV2") (pin "11") (pinfunction "11_11") (pintype "passive"))
    )
    (net (code "75") (name "TGT_SWCLK1") (class "Default")
      (node (ref "IC2") (pin "16") (pinfunction "TGT_SWCLK_16") (pintype "bidirectional"))
      (node (ref "SV2") (pin "12") (pinfunction "12_12") (pintype "passive"))
    )
    (net (code "76") (name "TGT_SWDIO") (class "Default")
      (node (ref "IC4") (pin "3") (pinfunction "TMS/SWDIO_3") (pintype "bidirectional"))
      (node (ref "SV2") (pin "9") (pinfunction "9_9") (pintype "passive"))
    )
    (net (code "77") (name "TGT_SWDIO1") (class "Default")
      (node (ref "IC2") (pin "17") (pinfunction "TGT_SWDIO_17") (pintype "bidirectional"))
      (node (ref "SV2") (pin "10") (pinfunction "10_10") (pintype "passive"))
    )
    (net (code "78") (name "TGT_SWO") (class "Default")
      (node (ref "IC4") (pin "1") (pinfunction "TDO/SWO_1") (pintype "bidirectional"))
      (node (ref "SV2") (pin "7") (pinfunction "7_7") (pintype "passive"))
    )
    (net (code "79") (name "TGT_SWO1") (class "Default")
      (node (ref "IC2") (pin "18") (pinfunction "TGT_SWO_18") (pintype "bidirectional"))
      (node (ref "SV2") (pin "8") (pinfunction "8_8") (pintype "passive"))
    )
    (net (code "80") (name "TGT_TX") (class "Default")
      (node (ref "IC4") (pin "98") (pinfunction "P0.2/TXD0/AD0.7_98") (pintype "bidirectional"))
      (node (ref "SV2") (pin "3") (pinfunction "3_3") (pintype "passive"))
    )
    (net (code "81") (name "TGT_TX1") (class "Default")
      (node (ref "IC2") (pin "31") (pinfunction "TGT_TX_31") (pintype "bidirectional"))
      (node (ref "SV2") (pin "4") (pinfunction "4_4") (pintype "passive"))
    )
    (net (code "82") (name "VBUS_IF") (class "Default")
      (node (ref "C1") (pin "1") (pinfunction "P$1_1") (pintype "passive"))
      (node (ref "CON1") (pin "VBUS") (pinfunction "VBUS_VBUS") (pintype "bidirectional"))
      (node (ref "D2") (pin "A") (pinfunction "A_A") (pintype "passive"))
      (node (ref "IC1") (pin "3") (pinfunction "IN_3") (pintype "input"))
    )
    (net (code "83") (name "VBUS_MIX") (class "Default")
      (node (ref "C11") (pin "1") (pinfunction "P$1_1") (pintype "passive"))
      (node (ref "D1") (pin "K") (pinfunction "K_K") (pintype "passive"))
      (node (ref "D2") (pin "K") (pinfunction "K_K") (pintype "passive"))
      (node (ref "IC3") (pin "3") (pinfunction "IN_3") (pintype "input"))
      (node (ref "SV4") (pin "3") (pinfunction "3_3") (pintype "passive"))
      (node (ref "SV4") (pin "4") (pinfunction "4_4") (pintype "passive"))
    )
    (net (code "84") (name "VBUS_TGT") (class "Default")
      (node (ref "CON2") (pin "VBUS") (pinfunction "VBUS_VBUS") (pintype "bidirectional"))
      (node (ref "D1") (pin "A") (pinfunction "A_A") (pintype "passive"))
    )
    (net (code "85") (name "unconnected-(IC4-P0.0{slash}CAN_RX1{slash}TXD3{slash}SDA1-Pad46)") (class "Default")
      (node (ref "IC4") (pin "46") (pinfunction "P0.0/CAN_RX1/TXD3/SDA1_46") (pintype "bidirectional"))
    )
    (net (code "86") (name "unconnected-(IC4-P0.1{slash}CAN_TX1{slash}RXD3{slash}SCL1-Pad47)") (class "Default")
      (node (ref "IC4") (pin "47") (pinfunction "P0.1/CAN_TX1/RXD3/SCL1_47") (pintype "bidirectional"))
    )
    (net (code "87") (name "unconnected-(IC4-P0.4{slash}I2SRX_CLK{slash}CAN_RX2{slash}CAP2.0-Pad81)") (class "Default")
      (node (ref "IC4") (pin "81") (pinfunction "P0.4/I2SRX_CLK/CAN_RX2/CAP2.0_81") (pintype "bidirectional"))
    )
    (net (code "88") (name "unconnected-(IC4-P0.5{slash}I2SRX_WS{slash}CAN_TX2{slash}CAP2.1-Pad80)") (class "Default")
      (node (ref "IC4") (pin "80") (pinfunction "P0.5/I2SRX_WS/CAN_TX2/CAP2.1_80") (pintype "bidirectional"))
    )
    (net (code "89") (name "unconnected-(IC4-P0.6{slash}I2SRX_SDA{slash}SSEL1{slash}MAT2.0-Pad79)") (class "Default")
      (node (ref "IC4") (pin "79") (pinfunction "P0.6/I2SRX_SDA/SSEL1/MAT2.0_79") (pintype "bidirectional"))
    )
    (net (code "90") (name "unconnected-(IC4-P0.7{slash}I2STX_CLK{slash}SCK1{slash}MAT2.1-Pad78)") (class "Default")
      (node (ref "IC4") (pin "78") (pinfunction "P0.7/I2STX_CLK/SCK1/MAT2.1_78") (pintype "bidirectional"))
    )
    (net (code "91") (name "unconnected-(IC4-P0.8{slash}I2STX_WS{slash}MISO1{slash}MAT2.2-Pad77)") (class "Default")
      (node (ref "IC4") (pin "77") (pinfunction "P0.8/I2STX_WS/MISO1/MAT2.2_77") (pintype "bidirectional"))
    )
    (net (code "92") (name "unconnected-(IC4-P0.9{slash}I2STX_SDA{slash}MOSI1{slash}MAT2.3-Pad76)") (class "Default")
      (node (ref "IC4") (pin "76") (pinfunction "P0.9/I2STX_SDA/MOSI1/MAT2.3_76") (pintype "bidirectional"))
    )
    (net (code "93") (name "unconnected-(IC4-P0.10{slash}TXD2{slash}SDA2{slash}MAT3.0-Pad48)") (class "Default")
      (node (ref "IC4") (pin "48") (pinfunction "P0.10/TXD2/SDA2/MAT3.0_48") (pintype "bidirectional"))
    )
    (net (code "94") (name "unconnected-(IC4-P0.11{slash}RXD2{slash}SCL2{slash}MAT3.1-Pad49)") (class "Default")
      (node (ref "IC4") (pin "49") (pinfunction "P0.11/RXD2/SCL2/MAT3.1_49") (pintype "bidirectional"))
    )
    (net (code "95") (name "unconnected-(IC4-P0.16{slash}RXD1{slash}SSEL0{slash}SSEL-Pad63)") (class "Default")
      (node (ref "IC4") (pin "63") (pinfunction "P0.16/RXD1/SSEL0/SSEL_63") (pintype "bidirectional"))
    )
    (net (code "96") (name "unconnected-(IC4-P0.17{slash}CTS1{slash}MISO0{slash}MISO-Pad61)") (class "Default")
      (node (ref "IC4") (pin "61") (pinfunction "P0.17/CTS1/MISO0/MISO_61") (pintype "bidirectional"))
    )
    (net (code "97") (name "unconnected-(IC4-P0.18{slash}DCD1{slash}MOSI0{slash}MOSI1-Pad60)") (class "Default")
      (node (ref "IC4") (pin "60") (pinfunction "P0.18/DCD1/MOSI0/MOSI1_60") (pintype "bidirectional"))
    )
    (net (code "98") (name "unconnected-(IC4-P0.19{slash}DSR1{slash}MCICLK{slash}SDA1-Pad59)") (class "Default")
      (node (ref "IC4") (pin "59") (pinfunction "P0.19/DSR1/MCICLK/SDA1_59") (pintype "bidirectional"))
    )
    (net (code "99") (name "unconnected-(IC4-P0.20{slash}DTR1{slash}SCL1-Pad58)") (class "Default")
      (node (ref "IC4") (pin "58") (pinfunction "P0.20/DTR1/SCL1_58") (pintype "bidirectional"))
    )
    (net (code "100") (name "unconnected-(IC4-P0.21{slash}RI1{slash}CAN_RX1-Pad57)") (class "Default")
      (node (ref "IC4") (pin "57") (pinfunction "P0.21/RI1/CAN_RX1_57") (pintype "bidirectional"))
    )
    (net (code "101") (name "unconnected-(IC4-P0.22{slash}RTS1{slash}CAN_TX1-Pad56)") (class "Default")
      (node (ref "IC4") (pin "56") (pinfunction "P0.22/RTS1/CAN_TX1_56") (pintype "bidirectional"))
    )
    (net (code "102") (name "unconnected-(IC4-P0.23{slash}AD0.0{slash}I2SRX_CLK{slash}CAP3.0-Pad9)") (class "Default")
      (node (ref "IC4") (pin "9") (pinfunction "P0.23/AD0.0/I2SRX_CLK/CAP3.0_9") (pintype "bidirectional"))
    )
    (net (code "103") (name "unconnected-(IC4-P0.24{slash}AD0.1{slash}I2SRX_WS{slash}CAP3.1-Pad8)") (class "Default")
      (node (ref "IC4") (pin "8") (pinfunction "P0.24/AD0.1/I2SRX_WS/CAP3.1_8") (pintype "bidirectional"))
    )
    (net (code "104") (name "unconnected-(IC4-P0.25{slash}AD0.2{slash}I2SRX_SDA{slash}TXD3-Pad7)") (class "Default")
      (node (ref "IC4") (pin "7") (pinfunction "P0.25/AD0.2/I2SRX_SDA/TXD3_7") (pintype "bidirectional"))
    )
    (net (code "105") (name "unconnected-(IC4-P0.26{slash}AD0.3{slash}AOUT{slash}RXD3-Pad6)") (class "Default")
      (node (ref "IC4") (pin "6") (pinfunction "P0.26/AD0.3/AOUT/RXD3_6") (pintype "bidirectional"))
    )
    (net (code "106") (name "unconnected-(IC4-P0.27{slash}SDA0{slash}USB_SDA-Pad25)") (class "Default")
      (node (ref "IC4") (pin "25") (pinfunction "P0.27/SDA0/USB_SDA_25") (pintype "bidirectional"))
    )
    (net (code "107") (name "unconnected-(IC4-P0.28{slash}SCL0{slash}USB_SCL-Pad24)") (class "Default")
      (node (ref "IC4") (pin "24") (pinfunction "P0.28/SCL0/USB_SCL_24") (pintype "bidirectional"))
    )
    (net (code "108") (name "unconnected-(IC4-P1.18{slash}USB_UP{slash}PWM1.1{slash}CAP1.0-Pad32)") (class "Default")
      (node (ref "IC4") (pin "32") (pinfunction "P1.18/USB_UP/PWM1.1/CAP1.0_32") (pintype "bidirectional"))
    )
    (net (code "109") (name "unconnected-(IC4-P1.19{slash}MC0A{slash}USB_PPWR{slash}CAP1.1-Pad33)") (class "Default")
      (node (ref "IC4") (pin "33") (pinfunction "P1.19/MC0A/USB_PPWR/CAP1.1_33") (pintype "bidirectional"))
    )
    (net (code "110") (name "unconnected-(IC4-P1.20{slash}MCFB0{slash}PWM1.2{slash}SCK0-Pad34)") (class "Default")
      (node (ref "IC4") (pin "34") (pinfunction "P1.20/MCFB0/PWM1.2/SCK0_34") (pintype "bidirectional"))
    )
    (net (code "111") (name "unconnected-(IC4-P1.21{slash}MCABORT{slash}PWM1.3{slash}SSEL0-Pad35)") (class "Default")
      (node (ref "IC4") (pin "35") (pinfunction "P1.21/MCABORT/PWM1.3/SSEL0_35") (pintype "bidirectional"))
    )
    (net (code "112") (name "unconnected-(IC4-P1.22{slash}MC0B{slash}USB_PWRD{slash}MAT1.0-Pad36)") (class "Default")
      (node (ref "IC4") (pin "36") (pinfunction "P1.22/MC0B/USB_PWRD/MAT1.0_36") (pintype "bidirectional"))
    )
    (net (code "113") (name "unconnected-(IC4-P1.23{slash}MCFB1{slash}PWM1.4{slash}MISO0-Pad37)") (class "Default")
      (node (ref "IC4") (pin "37") (pinfunction "P1.23/MCFB1/PWM1.4/MISO0_37") (pintype "bidirectional"))
    )
    (net (code "114") (name "unconnected-(IC4-P1.24{slash}MCFB2{slash}PWM1.5{slash}MOSI0-Pad38)") (class "Default")
      (node (ref "IC4") (pin "38") (pinfunction "P1.24/MCFB2/PWM1.5/MOSI0_38") (pintype "bidirectional"))
    )
    (net (code "115") (name "unconnected-(IC4-P1.29{slash}MC2B{slash}PCAP1.1{slash}MAT0.1-Pad45)") (class "Default")
      (node (ref "IC4") (pin "45") (pinfunction "P1.29/MC2B/PCAP1.1/MAT0.1_45") (pintype "bidirectional"))
    )
    (net (code "116") (name "unconnected-(IC4-P1.30{slash}VBUS{slash}AD0.4-Pad21)") (class "Default")
      (node (ref "IC4") (pin "21") (pinfunction "P1.30/VBUS/AD0.4_21") (pintype "bidirectional"))
    )
    (net (code "117") (name "unconnected-(IC4-P1.31{slash}SCK1{slash}AD0.5-Pad20)") (class "Default")
      (node (ref "IC4") (pin "20") (pinfunction "P1.31/SCK1/AD0.5_20") (pintype "bidirectional"))
    )
    (net (code "118") (name "unconnected-(IC4-P2.8{slash}CAN_TX2{slash}TXD2-Pad65)") (class "Default")
      (node (ref "IC4") (pin "65") (pinfunction "P2.8/CAN_TX2/TXD2_65") (pintype "bidirectional"))
    )
    (net (code "119") (name "unconnected-(IC4-P2.11{slash}EINT1N{slash}I2STX_CLK-Pad52)") (class "Default")
      (node (ref "IC4") (pin "52") (pinfunction "P2.11/EINT1N/I2STX_CLK_52") (pintype "bidirectional"))
    )
    (net (code "120") (name "unconnected-(IC4-P2.12{slash}EINT2N{slash}I2STX_WS-Pad51)") (class "Default")
      (node (ref "IC4") (pin "51") (pinfunction "P2.12/EINT2N/I2STX_WS_51") (pintype "bidirectional"))
    )
    (net (code "121") (name "unconnected-(IC4-P2.13{slash}EINT3N{slash}I2STX_SDA-Pad50)") (class "Default")
      (node (ref "IC4") (pin "50") (pinfunction "P2.13/EINT3N/I2STX_SDA_50") (pintype "bidirectional"))
    )
    (net (code "122") (name "unconnected-(IC4-P3.25{slash}MAT0.0{slash}PWM1.2-Pad27)") (class "Default")
      (node (ref "IC4") (pin "27") (pinfunction "P3.25/MAT0.0/PWM1.2_27") (pintype "bidirectional"))
    )
    (net (code "123") (name "unconnected-(IC4-P3.26{slash}STCLK{slash}MAT0.1{slash}PWM1.3-Pad26)") (class "Default")
      (node (ref "IC4") (pin "26") (pinfunction "P3.26/STCLK/MAT0.1/PWM1.3_26") (pintype "bidirectional"))
    )
    (net (code "124") (name "unconnected-(IC4-P4.28{slash}RX_MCLK{slash}MAT2.0{slash}TXD3-Pad82)") (class "Default")
      (node (ref "IC4") (pin "82") (pinfunction "P4.28/RX_MCLK/MAT2.0/TXD3_82") (pintype "bidirectional"))
    )
    (net (code "125") (name "unconnected-(IC4-P4.29{slash}TX_MCLK{slash}MAT2.1{slash}RXD3-Pad85)") (class "Default")
      (node (ref "IC4") (pin "85") (pinfunction "P4.29/TX_MCLK/MAT2.1/RXD3_85") (pintype "bidirectional"))
    )
    (net (code "126") (name "unconnected-(IC4-RSTOUTN-Pad14)") (class "Default")
      (node (ref "IC4") (pin "14") (pinfunction "RSTOUTN_14") (pintype "bidirectional"))
    )
    (net (code "127") (name "unconnected-(IC4-RTCK-Pad100)") (class "Default")
      (node (ref "IC4") (pin "100") (pinfunction "RTCK_100") (pintype "bidirectional"))
    )
    (net (code "128") (name "unconnected-(IC4-TDI-Pad2)") (class "Default")
      (node (ref "IC4") (pin "2") (pinfunction "TDI_2") (pintype "bidirectional"))
    )
    (net (code "129") (name "unconnected-(IC4-TRST_N-Pad4)") (class "Default")
      (node (ref "IC4") (pin "4") (pinfunction "TRST_N_4") (pintype "bidirectional"))
    )
    (net (code "130") (name "unconnected-(IC4-VBAT-Pad19)") (class "Default")
      (node (ref "IC4") (pin "19") (pinfunction "VBAT_19") (pintype "bidirectional"))
    )
  )
)
